# WoordklokCharles.net
KiCad netlist of a schematic drawn in EAGLE
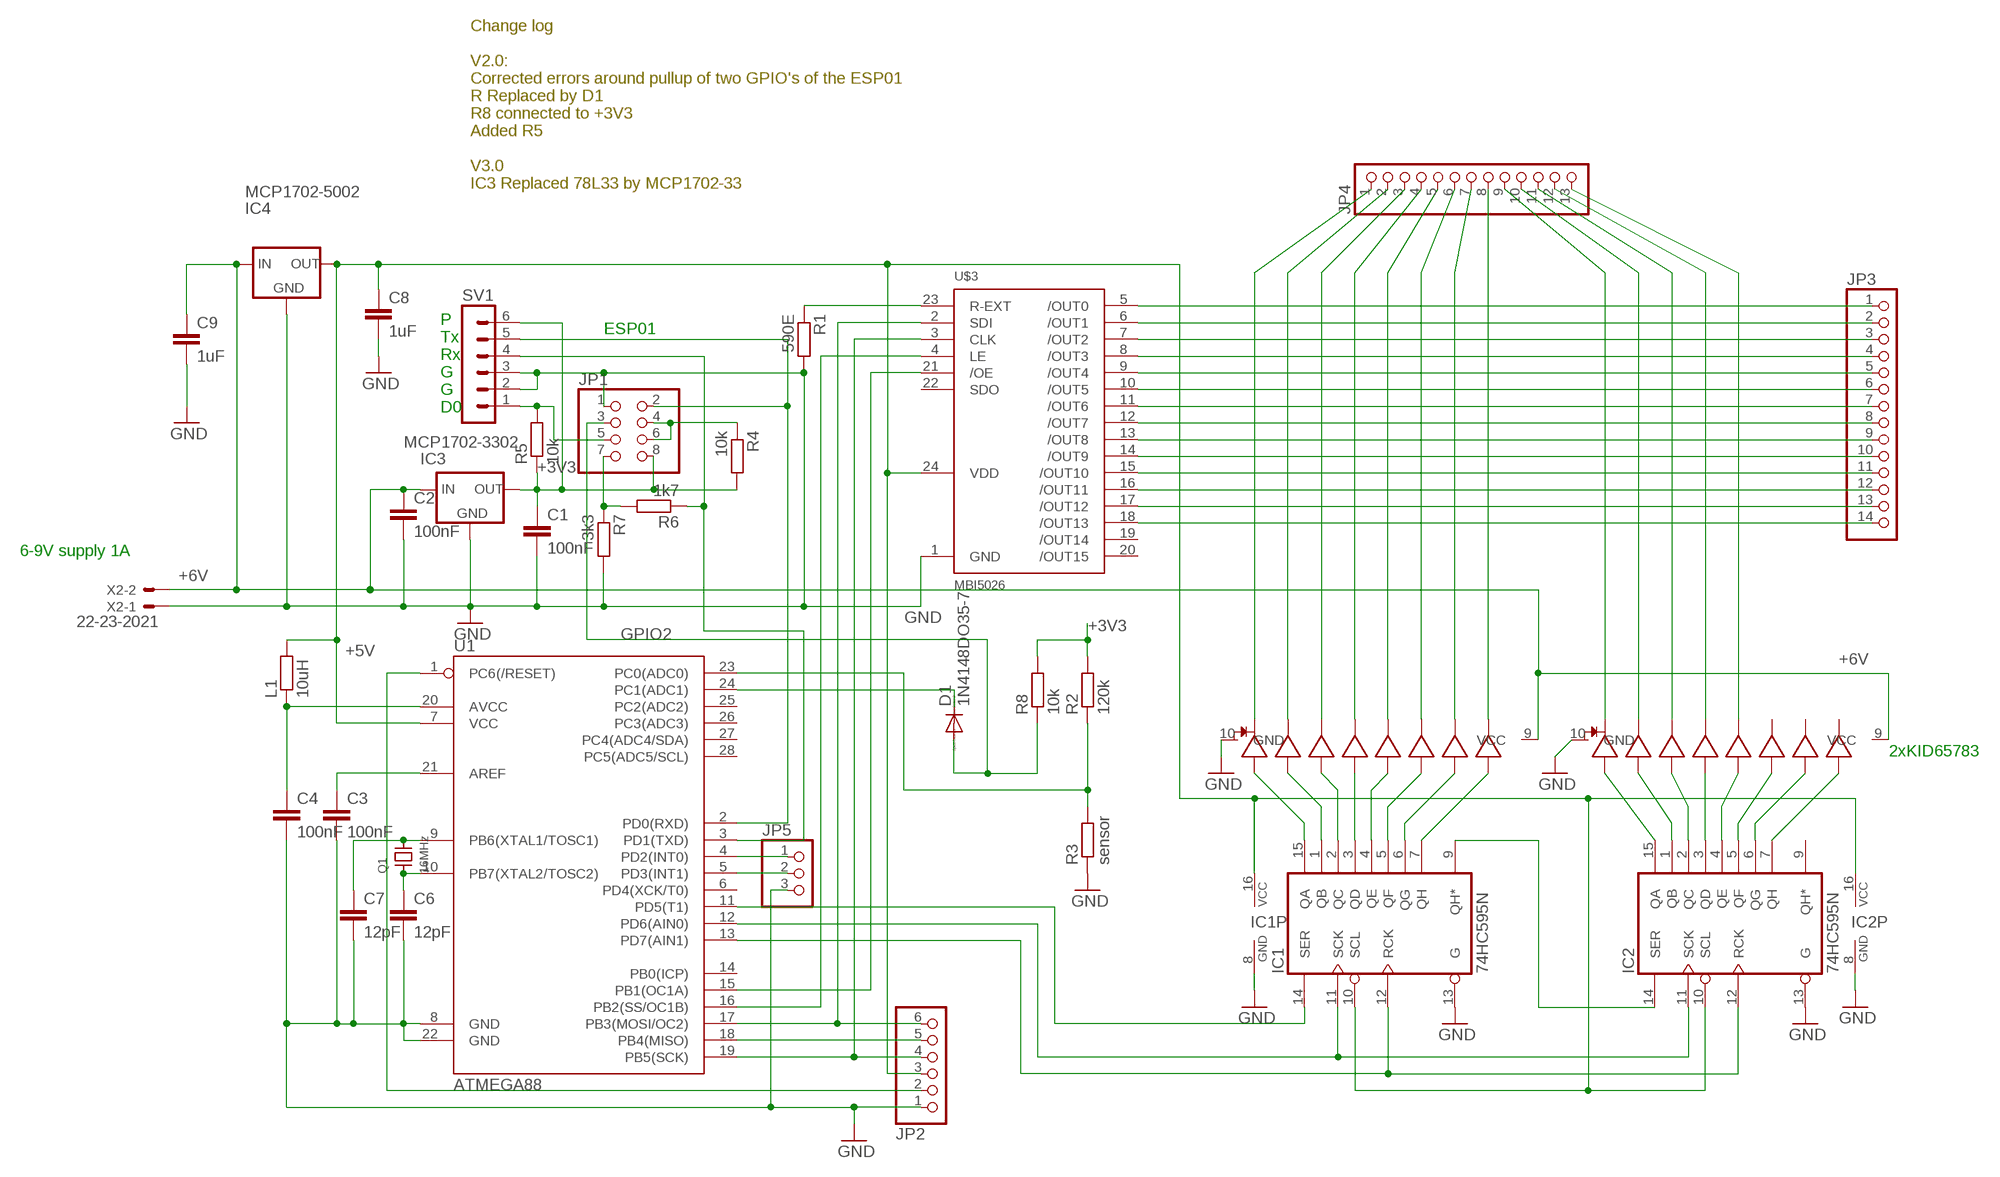
[diagram p0: schematic, sheet 1]

(export (version "E")
  (design (tool "Eeschema 10.0.6"))
  (components
    (comp (ref "C1")
      (value "100nF")
      (footprint "eagle-import:C025-024X044")
      (libsource (lib "eagle-import") (part "C-EU025-024X044"))
    )
    (comp (ref "C2")
      (value "100nF")
      (footprint "eagle-import:C025-024X044")
      (libsource (lib "eagle-import") (part "C-EU025-024X044"))
    )
    (comp (ref "C3")
      (value "100nF")
      (footprint "eagle-import:C025-024X044")
      (libsource (lib "eagle-import") (part "C-EU025-024X044"))
    )
    (comp (ref "C4")
      (value "100nF")
      (footprint "eagle-import:C025-024X044")
      (libsource (lib "eagle-import") (part "C-EU025-024X044"))
    )
    (comp (ref "C6")
      (value "12pF")
      (footprint "eagle-import:C025-024X044")
      (libsource (lib "eagle-import") (part "C-EU025-024X044"))
    )
    (comp (ref "C7")
      (value "12pF")
      (footprint "eagle-import:C025-024X044")
      (libsource (lib "eagle-import") (part "C-EU025-024X044"))
    )
    (comp (ref "C8")
      (value "1uF")
      (footprint "eagle-import:C025-024X044")
      (libsource (lib "eagle-import") (part "C-EU025-024X044"))
    )
    (comp (ref "C9")
      (value "1uF")
      (footprint "eagle-import:C025-024X044")
      (libsource (lib "eagle-import") (part "C-EU025-024X044"))
    )
    (comp (ref "D1")
      (value "1N4148DO35-7")
      (footprint "eagle-import:DO35-7")
      (libsource (lib "eagle-import") (part "1N4148DO35-7"))
    )
    (comp (ref "IC1")
      (value "74HC595N")
      (footprint "eagle-import:DIL16")
      (libsource (lib "eagle-import") (part "74595NHC"))
    )
    (comp (ref "IC2")
      (value "74HC595N")
      (footprint "eagle-import:DIL16")
      (libsource (lib "eagle-import") (part "74595NHC"))
    )
    (comp (ref "IC3")
      (value "MCP1702-3302")
      (footprint "eagle-import:TO92")
      (libsource (lib "eagle-import") (part "MCP1700TRI"))
    )
    (comp (ref "IC4")
      (value "MCP1702-5002")
      (footprint "eagle-import:TO92")
      (libsource (lib "eagle-import") (part "MCP1700TRI"))
    )
    (comp (ref "JP1")
      (value "PINHD-2X4")
      (footprint "eagle-import:2X04")
      (libsource (lib "eagle-import") (part "PINHD-2X4"))
    )
    (comp (ref "JP2")
      (value "PINHD-1X6")
      (footprint "eagle-import:1X06")
      (libsource (lib "eagle-import") (part "PINHD-1X6"))
    )
    (comp (ref "JP3")
      (value "PINHD-1X14")
      (footprint "eagle-import:1X14")
      (libsource (lib "eagle-import") (part "PINHD-1X14"))
    )
    (comp (ref "JP4")
      (value "PINHD-1X13")
      (footprint "eagle-import:1X13")
      (libsource (lib "eagle-import") (part "PINHD-1X13"))
    )
    (comp (ref "JP5")
      (value "PINHD-1X3")
      (footprint "eagle-import:1X03")
      (libsource (lib "eagle-import") (part "PINHD-1X3"))
    )
    (comp (ref "L1")
      (value "10uH")
      (footprint "eagle-import:0204_7")
      (libsource (lib "eagle-import") (part "R-EU_0204/7"))
    )
    (comp (ref "Q1")
      (value "16MHz")
      (footprint "eagle-import:XTAL")
      (libsource (lib "eagle-import") (part "XTAL"))
    )
    (comp (ref "R1")
      (value "590E")
      (footprint "eagle-import:0204_7")
      (libsource (lib "eagle-import") (part "R-EU_0204/7"))
    )
    (comp (ref "R2")
      (value "120k")
      (footprint "eagle-import:0204_7")
      (libsource (lib "eagle-import") (part "R-EU_0204/7"))
    )
    (comp (ref "R3")
      (value "sensor")
      (footprint "eagle-import:0204_7")
      (libsource (lib "eagle-import") (part "R-EU_0204/7"))
    )
    (comp (ref "R4")
      (value "10k")
      (footprint "eagle-import:0204V")
      (libsource (lib "eagle-import") (part "R-EU_0204/2V"))
    )
    (comp (ref "R5")
      (value "10k")
      (footprint "eagle-import:0204V")
      (libsource (lib "eagle-import") (part "R-EU_0204/2V"))
    )
    (comp (ref "R6")
      (value "1k7")
      (footprint "eagle-import:0204_7")
      (libsource (lib "eagle-import") (part "R-EU_0204/7"))
    )
    (comp (ref "R7")
      (value "3k3")
      (footprint "eagle-import:0204_7")
      (libsource (lib "eagle-import") (part "R-EU_0204/7"))
    )
    (comp (ref "R8")
      (value "10k")
      (footprint "eagle-import:0204_7")
      (libsource (lib "eagle-import") (part "R-EU_0204/7"))
    )
    (comp (ref "SV1")
      (value "MA06-1")
      (footprint "eagle-import:MA06-1")
      (libsource (lib "eagle-import") (part "MA06-1"))
    )
    (comp (ref "U$1")
      (value "KID65783")
      (footprint "eagle-import:DIP18")
      (libsource (lib "eagle-import") (part "KID65783DIPDIP18"))
    )
    (comp (ref "U$2")
      (value "KID65783")
      (footprint "eagle-import:DIP18")
      (libsource (lib "eagle-import") (part "KID65783DIPDIP18"))
    )
    (comp (ref "U$3")
      (value "MBI5026")
      (footprint "eagle-import:DIP24")
      (libsource (lib "eagle-import") (part "MBI5026DIP"))
    )
    (comp (ref "U1")
      (value "ATMEGA88")
      (footprint "eagle-import:DIL28-3")
      (libsource (lib "eagle-import") (part "ATMEGA328P_PDIP"))
    )
    (comp (ref "X2")
      (value "22-23-2021")
      (footprint "eagle-import:22-23-2021")
      (fields (field (name "MF") "MOLEX"))
      (libsource (lib "eagle-import") (part "22-23-2021"))
    )
  )
  (nets
    (net (code "1") (name "/+3V3") (class "Default")
      (node (ref "C1") (pin "1") (pinfunction "1_1") (pintype "passive"))
      (node (ref "IC3") (pin "3") (pinfunction "OUT_3") (pintype "passive"))
      (node (ref "JP1") (pin "8") (pinfunction "8_8") (pintype "passive"))
      (node (ref "R2") (pin "2") (pinfunction "2_2") (pintype "passive"))
      (node (ref "R4") (pin "2") (pinfunction "2_2") (pintype "passive"))
      (node (ref "R5") (pin "1") (pinfunction "1_1") (pintype "passive"))
      (node (ref "R8") (pin "2") (pinfunction "2_2") (pintype "passive"))
      (node (ref "SV1") (pin "6") (pinfunction "6_6") (pintype "passive"))
    )
    (net (code "2") (name "/+5V") (class "Default")
      (node (ref "C8") (pin "1") (pinfunction "1_1") (pintype "passive"))
      (node (ref "IC1") (pin "10") (pinfunction "SCL_10") (pintype "input"))
      (node (ref "IC1") (pin "16") (pinfunction "VCC_16") (pintype "power_in"))
      (node (ref "IC2") (pin "10") (pinfunction "SCL_10") (pintype "input"))
      (node (ref "IC2") (pin "16") (pinfunction "VCC_16") (pintype "power_in"))
      (node (ref "IC4") (pin "3") (pinfunction "OUT_3") (pintype "passive"))
      (node (ref "JP2") (pin "3") (pinfunction "3_3") (pintype "passive"))
      (node (ref "L1") (pin "2") (pinfunction "2_2") (pintype "passive"))
      (node (ref "U$3") (pin "24") (pinfunction "VDD_24") (pintype "bidirectional"))
      (node (ref "U1") (pin "7") (pinfunction "VCC_7") (pintype "bidirectional"))
    )
    (net (code "3") (name "/+6V") (class "Default")
      (node (ref "C2") (pin "1") (pinfunction "1_1") (pintype "passive"))
      (node (ref "C9") (pin "1") (pinfunction "1_1") (pintype "passive"))
      (node (ref "IC3") (pin "2") (pinfunction "IN_2") (pintype "input"))
      (node (ref "IC4") (pin "2") (pinfunction "IN_2") (pintype "input"))
      (node (ref "U$1") (pin "9") (pinfunction "VCC_9") (pintype "power_in"))
      (node (ref "U$2") (pin "9") (pinfunction "VCC_9") (pintype "power_in"))
      (node (ref "X2") (pin "2") (pinfunction "S_2") (pintype "passive"))
    )
    (net (code "4") (name "/GPIO2") (class "Default")
      (node (ref "D1") (pin "A") (pinfunction "A_A") (pintype "passive"))
      (node (ref "JP1") (pin "3") (pinfunction "3_3") (pintype "passive"))
      (node (ref "R8") (pin "1") (pinfunction "1_1") (pintype "passive"))
    )
    (net (code "5") (name "GND") (class "Default")
      (node (ref "C1") (pin "2") (pinfunction "2_2") (pintype "passive"))
      (node (ref "C2") (pin "2") (pinfunction "2_2") (pintype "passive"))
      (node (ref "C3") (pin "2") (pinfunction "2_2") (pintype "passive"))
      (node (ref "C4") (pin "2") (pinfunction "2_2") (pintype "passive"))
      (node (ref "C6") (pin "2") (pinfunction "2_2") (pintype "passive"))
      (node (ref "C7") (pin "2") (pinfunction "2_2") (pintype "passive"))
      (node (ref "C8") (pin "2") (pinfunction "2_2") (pintype "passive"))
      (node (ref "C9") (pin "2") (pinfunction "2_2") (pintype "passive"))
      (node (ref "IC1") (pin "13") (pinfunction "G_13") (pintype "input"))
      (node (ref "IC1") (pin "8") (pinfunction "GND_8") (pintype "power_in"))
      (node (ref "IC2") (pin "13") (pinfunction "G_13") (pintype "input"))
      (node (ref "IC2") (pin "8") (pinfunction "GND_8") (pintype "power_in"))
      (node (ref "IC3") (pin "1") (pinfunction "GND_1") (pintype "input"))
      (node (ref "IC4") (pin "1") (pinfunction "GND_1") (pintype "input"))
      (node (ref "JP1") (pin "1") (pinfunction "1_1") (pintype "passive"))
      (node (ref "JP2") (pin "1") (pinfunction "1_1") (pintype "passive"))
      (node (ref "JP5") (pin "3") (pinfunction "3_3") (pintype "passive"))
      (node (ref "R1") (pin "2") (pinfunction "2_2") (pintype "passive"))
      (node (ref "R3") (pin "1") (pinfunction "1_1") (pintype "passive"))
      (node (ref "R7") (pin "2") (pinfunction "2_2") (pintype "passive"))
      (node (ref "SV1") (pin "2") (pinfunction "2_2") (pintype "passive"))
      (node (ref "SV1") (pin "3") (pinfunction "3_3") (pintype "passive"))
      (node (ref "U$1") (pin "10") (pinfunction "GND_10") (pintype "power_in"))
      (node (ref "U$2") (pin "10") (pinfunction "GND_10") (pintype "power_in"))
      (node (ref "U$3") (pin "1") (pinfunction "GND_1") (pintype "bidirectional"))
      (node (ref "U1") (pin "22") (pinfunction "GND_22") (pintype "bidirectional"))
      (node (ref "U1") (pin "8") (pinfunction "GND_8") (pintype "bidirectional"))
      (node (ref "X2") (pin "1") (pinfunction "S_1") (pintype "passive"))
    )
    (net (code "6") (name "Net-(IC1A-QA)") (class "Default")
      (node (ref "IC1") (pin "15") (pinfunction "QA_15") (pintype "tri_state"))
      (node (ref "U$1") (pin "8") (pinfunction "IN7_8") (pintype "input"))
    )
    (net (code "7") (name "Net-(IC1A-QB)") (class "Default")
      (node (ref "IC1") (pin "1") (pinfunction "QB_1") (pintype "tri_state"))
      (node (ref "U$1") (pin "7") (pinfunction "IN6_7") (pintype "input"))
    )
    (net (code "8") (name "Net-(IC1A-QC)") (class "Default")
      (node (ref "IC1") (pin "2") (pinfunction "QC_2") (pintype "tri_state"))
      (node (ref "U$1") (pin "6") (pinfunction "IN5_6") (pintype "input"))
    )
    (net (code "9") (name "Net-(IC1A-QD)") (class "Default")
      (node (ref "IC1") (pin "3") (pinfunction "QD_3") (pintype "tri_state"))
      (node (ref "U$1") (pin "5") (pinfunction "IN4_5") (pintype "input"))
    )
    (net (code "10") (name "Net-(IC1A-QE)") (class "Default")
      (node (ref "IC1") (pin "4") (pinfunction "QE_4") (pintype "tri_state"))
      (node (ref "U$1") (pin "4") (pinfunction "IN3_4") (pintype "input"))
    )
    (net (code "11") (name "Net-(IC1A-QF)") (class "Default")
      (node (ref "IC1") (pin "5") (pinfunction "QF_5") (pintype "tri_state"))
      (node (ref "U$1") (pin "3") (pinfunction "IN2_3") (pintype "input"))
    )
    (net (code "12") (name "Net-(IC1A-QG)") (class "Default")
      (node (ref "IC1") (pin "6") (pinfunction "QG_6") (pintype "tri_state"))
      (node (ref "U$1") (pin "2") (pinfunction "IN1_2") (pintype "input"))
    )
    (net (code "13") (name "Net-(IC1A-QH)") (class "Default")
      (node (ref "IC1") (pin "7") (pinfunction "QH_7") (pintype "tri_state"))
      (node (ref "U$1") (pin "1") (pinfunction "IN0_1") (pintype "input"))
    )
    (net (code "14") (name "Net-(IC1A-QH*)") (class "Default")
      (node (ref "IC1") (pin "9") (pinfunction "QH*_9") (pintype "tri_state"))
      (node (ref "IC2") (pin "14") (pinfunction "SER_14") (pintype "input"))
    )
    (net (code "15") (name "Net-(IC1A-RCK)") (class "Default")
      (node (ref "IC1") (pin "12") (pinfunction "RCK_12") (pintype "input"))
      (node (ref "IC2") (pin "12") (pinfunction "RCK_12") (pintype "input"))
      (node (ref "U1") (pin "13") (pinfunction "PD7(AIN1)_13") (pintype "bidirectional"))
    )
    (net (code "16") (name "Net-(IC1A-SCK)") (class "Default")
      (node (ref "IC1") (pin "11") (pinfunction "SCK_11") (pintype "input"))
      (node (ref "IC2") (pin "11") (pinfunction "SCK_11") (pintype "input"))
      (node (ref "U1") (pin "12") (pinfunction "PD6(AIN0)_12") (pintype "bidirectional"))
    )
    (net (code "17") (name "Net-(IC1A-SER)") (class "Default")
      (node (ref "IC1") (pin "14") (pinfunction "SER_14") (pintype "input"))
      (node (ref "U1") (pin "11") (pinfunction "PD5(T1)_11") (pintype "bidirectional"))
    )
    (net (code "18") (name "Net-(IC2A-QA)") (class "Default")
      (node (ref "IC2") (pin "15") (pinfunction "QA_15") (pintype "tri_state"))
      (node (ref "U$2") (pin "8") (pinfunction "IN7_8") (pintype "input"))
    )
    (net (code "19") (name "Net-(IC2A-QB)") (class "Default")
      (node (ref "IC2") (pin "1") (pinfunction "QB_1") (pintype "tri_state"))
      (node (ref "U$2") (pin "7") (pinfunction "IN6_7") (pintype "input"))
    )
    (net (code "20") (name "Net-(IC2A-QC)") (class "Default")
      (node (ref "IC2") (pin "2") (pinfunction "QC_2") (pintype "tri_state"))
      (node (ref "U$2") (pin "6") (pinfunction "IN5_6") (pintype "input"))
    )
    (net (code "21") (name "Net-(IC2A-QD)") (class "Default")
      (node (ref "IC2") (pin "3") (pinfunction "QD_3") (pintype "tri_state"))
      (node (ref "U$2") (pin "5") (pinfunction "IN4_5") (pintype "input"))
    )
    (net (code "22") (name "Net-(IC2A-QE)") (class "Default")
      (node (ref "IC2") (pin "4") (pinfunction "QE_4") (pintype "tri_state"))
      (node (ref "U$2") (pin "4") (pinfunction "IN3_4") (pintype "input"))
    )
    (net (code "23") (name "Net-(IC2A-QF)") (class "Default")
      (node (ref "IC2") (pin "5") (pinfunction "QF_5") (pintype "tri_state"))
      (node (ref "U$2") (pin "3") (pinfunction "IN2_3") (pintype "input"))
    )
    (net (code "24") (name "Net-(IC2A-QG)") (class "Default")
      (node (ref "IC2") (pin "6") (pinfunction "QG_6") (pintype "tri_state"))
      (node (ref "U$2") (pin "2") (pinfunction "IN1_2") (pintype "input"))
    )
    (net (code "25") (name "Net-(IC2A-QH)") (class "Default")
      (node (ref "IC2") (pin "7") (pinfunction "QH_7") (pintype "tri_state"))
      (node (ref "U$2") (pin "1") (pinfunction "IN0_1") (pintype "input"))
    )
    (net (code "26") (name "Net-(JP1-Pad4)") (class "Default")
      (node (ref "JP1") (pin "4") (pinfunction "4_4") (pintype "passive"))
      (node (ref "JP1") (pin "6") (pinfunction "6_6") (pintype "passive"))
      (node (ref "R4") (pin "1") (pinfunction "1_1") (pintype "passive"))
    )
    (net (code "27") (name "Net-(JP1-Pad5)") (class "Default")
      (node (ref "JP1") (pin "5") (pinfunction "5_5") (pintype "passive"))
      (node (ref "R5") (pin "2") (pinfunction "2_2") (pintype "passive"))
      (node (ref "SV1") (pin "1") (pinfunction "1_1") (pintype "passive"))
    )
    (net (code "28") (name "Net-(JP1-Pad7)") (class "Default")
      (node (ref "JP1") (pin "7") (pinfunction "7_7") (pintype "passive"))
      (node (ref "R6") (pin "2") (pinfunction "2_2") (pintype "passive"))
      (node (ref "R7") (pin "1") (pinfunction "1_1") (pintype "passive"))
    )
    (net (code "29") (name "Net-(U$1-OUT0)") (class "Default")
      (node (ref "JP4") (pin "8") (pinfunction "8_8") (pintype "passive"))
      (node (ref "U$1") (pin "18") (pinfunction "OUT0_18") (pintype "output"))
    )
    (net (code "30") (name "Net-(U$1-OUT1)") (class "Default")
      (node (ref "JP4") (pin "7") (pinfunction "7_7") (pintype "passive"))
      (node (ref "U$1") (pin "17") (pinfunction "OUT1_17") (pintype "output"))
    )
    (net (code "31") (name "Net-(U$1-OUT2)") (class "Default")
      (node (ref "JP4") (pin "6") (pinfunction "6_6") (pintype "passive"))
      (node (ref "U$1") (pin "16") (pinfunction "OUT2_16") (pintype "output"))
    )
    (net (code "32") (name "Net-(U$1-OUT3)") (class "Default")
      (node (ref "JP4") (pin "5") (pinfunction "5_5") (pintype "passive"))
      (node (ref "U$1") (pin "15") (pinfunction "OUT3_15") (pintype "output"))
    )
    (net (code "33") (name "Net-(U$1-OUT4)") (class "Default")
      (node (ref "JP4") (pin "4") (pinfunction "4_4") (pintype "passive"))
      (node (ref "U$1") (pin "14") (pinfunction "OUT4_14") (pintype "output"))
    )
    (net (code "34") (name "Net-(U$1-OUT5)") (class "Default")
      (node (ref "JP4") (pin "3") (pinfunction "3_3") (pintype "passive"))
      (node (ref "U$1") (pin "13") (pinfunction "OUT5_13") (pintype "output"))
    )
    (net (code "35") (name "Net-(U$1-OUT6)") (class "Default")
      (node (ref "JP4") (pin "2") (pinfunction "2_2") (pintype "passive"))
      (node (ref "U$1") (pin "12") (pinfunction "OUT6_12") (pintype "output"))
    )
    (net (code "36") (name "Net-(U$1-OUT7)") (class "Default")
      (node (ref "JP4") (pin "1") (pinfunction "1_1") (pintype "passive"))
      (node (ref "U$1") (pin "11") (pinfunction "OUT7_11") (pintype "output"))
    )
    (net (code "37") (name "Net-(U$2-OUT3)") (class "Default")
      (node (ref "JP4") (pin "13") (pinfunction "13_13") (pintype "passive"))
      (node (ref "U$2") (pin "15") (pinfunction "OUT3_15") (pintype "output"))
    )
    (net (code "38") (name "Net-(U$2-OUT4)") (class "Default")
      (node (ref "JP4") (pin "12") (pinfunction "12_12") (pintype "passive"))
      (node (ref "U$2") (pin "14") (pinfunction "OUT4_14") (pintype "output"))
    )
    (net (code "39") (name "Net-(U$2-OUT5)") (class "Default")
      (node (ref "JP4") (pin "11") (pinfunction "11_11") (pintype "passive"))
      (node (ref "U$2") (pin "13") (pinfunction "OUT5_13") (pintype "output"))
    )
    (net (code "40") (name "Net-(U$2-OUT6)") (class "Default")
      (node (ref "JP4") (pin "10") (pinfunction "10_10") (pintype "passive"))
      (node (ref "U$2") (pin "12") (pinfunction "OUT6_12") (pintype "output"))
    )
    (net (code "41") (name "Net-(U$2-OUT7)") (class "Default")
      (node (ref "JP4") (pin "9") (pinfunction "9_9") (pintype "passive"))
      (node (ref "U$2") (pin "11") (pinfunction "OUT7_11") (pintype "output"))
    )
    (net (code "42") (name "Net-(U$3-CLK)") (class "Default")
      (node (ref "JP2") (pin "4") (pinfunction "4_4") (pintype "passive"))
      (node (ref "U$3") (pin "3") (pinfunction "CLK_3") (pintype "bidirectional"))
      (node (ref "U1") (pin "19") (pinfunction "PB5(SCK)_19") (pintype "bidirectional"))
    )
    (net (code "43") (name "Net-(U$3-LE)") (class "Default")
      (node (ref "U$3") (pin "4") (pinfunction "LE_4") (pintype "bidirectional"))
      (node (ref "U1") (pin "16") (pinfunction "PB2(SS/OC1B)_16") (pintype "bidirectional"))
    )
    (net (code "44") (name "Net-(U$3-R-EXT)") (class "Default")
      (node (ref "R1") (pin "1") (pinfunction "1_1") (pintype "passive"))
      (node (ref "U$3") (pin "23") (pinfunction "R-EXT_23") (pintype "bidirectional"))
    )
    (net (code "45") (name "Net-(U$3-SDI)") (class "Default")
      (node (ref "JP2") (pin "6") (pinfunction "6_6") (pintype "passive"))
      (node (ref "U$3") (pin "2") (pinfunction "SDI_2") (pintype "bidirectional"))
      (node (ref "U1") (pin "17") (pinfunction "PB3(MOSI/OC2)_17") (pintype "bidirectional"))
    )
    (net (code "46") (name "Net-(U$3-{slash}OE)") (class "Default")
      (node (ref "U$3") (pin "21") (pinfunction "/OE_21") (pintype "bidirectional"))
      (node (ref "U1") (pin "15") (pinfunction "PB1(OC1A)_15") (pintype "bidirectional"))
    )
    (net (code "47") (name "Net-(U$3-{slash}OUT0)") (class "Default")
      (node (ref "JP3") (pin "1") (pinfunction "1_1") (pintype "passive"))
      (node (ref "U$3") (pin "5") (pinfunction "/OUT0_5") (pintype "bidirectional"))
    )
    (net (code "48") (name "Net-(U$3-{slash}OUT1)") (class "Default")
      (node (ref "JP3") (pin "2") (pinfunction "2_2") (pintype "passive"))
      (node (ref "U$3") (pin "6") (pinfunction "/OUT1_6") (pintype "bidirectional"))
    )
    (net (code "49") (name "Net-(U$3-{slash}OUT2)") (class "Default")
      (node (ref "JP3") (pin "3") (pinfunction "3_3") (pintype "passive"))
      (node (ref "U$3") (pin "7") (pinfunction "/OUT2_7") (pintype "bidirectional"))
    )
    (net (code "50") (name "Net-(U$3-{slash}OUT3)") (class "Default")
      (node (ref "JP3") (pin "4") (pinfunction "4_4") (pintype "passive"))
      (node (ref "U$3") (pin "8") (pinfunction "/OUT3_8") (pintype "bidirectional"))
    )
    (net (code "51") (name "Net-(U$3-{slash}OUT4)") (class "Default")
      (node (ref "JP3") (pin "5") (pinfunction "5_5") (pintype "passive"))
      (node (ref "U$3") (pin "9") (pinfunction "/OUT4_9") (pintype "bidirectional"))
    )
    (net (code "52") (name "Net-(U$3-{slash}OUT5)") (class "Default")
      (node (ref "JP3") (pin "6") (pinfunction "6_6") (pintype "passive"))
      (node (ref "U$3") (pin "10") (pinfunction "/OUT5_10") (pintype "bidirectional"))
    )
    (net (code "53") (name "Net-(U$3-{slash}OUT6)") (class "Default")
      (node (ref "JP3") (pin "7") (pinfunction "7_7") (pintype "passive"))
      (node (ref "U$3") (pin "11") (pinfunction "/OUT6_11") (pintype "bidirectional"))
    )
    (net (code "54") (name "Net-(U$3-{slash}OUT7)") (class "Default")
      (node (ref "JP3") (pin "8") (pinfunction "8_8") (pintype "passive"))
      (node (ref "U$3") (pin "12") (pinfunction "/OUT7_12") (pintype "bidirectional"))
    )
    (net (code "55") (name "Net-(U$3-{slash}OUT8)") (class "Default")
      (node (ref "JP3") (pin "9") (pinfunction "9_9") (pintype "passive"))
      (node (ref "U$3") (pin "13") (pinfunction "/OUT8_13") (pintype "bidirectional"))
    )
    (net (code "56") (name "Net-(U$3-{slash}OUT9)") (class "Default")
      (node (ref "JP3") (pin "10") (pinfunction "10_10") (pintype "passive"))
      (node (ref "U$3") (pin "14") (pinfunction "/OUT9_14") (pintype "bidirectional"))
    )
    (net (code "57") (name "Net-(U$3-{slash}OUT10)") (class "Default")
      (node (ref "JP3") (pin "11") (pinfunction "11_11") (pintype "passive"))
      (node (ref "U$3") (pin "15") (pinfunction "/OUT10_15") (pintype "bidirectional"))
    )
    (net (code "58") (name "Net-(U$3-{slash}OUT11)") (class "Default")
      (node (ref "JP3") (pin "12") (pinfunction "12_12") (pintype "passive"))
      (node (ref "U$3") (pin "16") (pinfunction "/OUT11_16") (pintype "bidirectional"))
    )
    (net (code "59") (name "Net-(U$3-{slash}OUT12)") (class "Default")
      (node (ref "JP3") (pin "13") (pinfunction "13_13") (pintype "passive"))
      (node (ref "U$3") (pin "17") (pinfunction "/OUT12_17") (pintype "bidirectional"))
    )
    (net (code "60") (name "Net-(U$3-{slash}OUT13)") (class "Default")
      (node (ref "JP3") (pin "14") (pinfunction "14_14") (pintype "passive"))
      (node (ref "U$3") (pin "18") (pinfunction "/OUT13_18") (pintype "bidirectional"))
    )
    (net (code "61") (name "Net-(U1-AREF)") (class "Default")
      (node (ref "C3") (pin "1") (pinfunction "1_1") (pintype "passive"))
      (node (ref "U1") (pin "21") (pinfunction "AREF_21") (pintype "bidirectional"))
    )
    (net (code "62") (name "Net-(U1-AVCC)") (class "Default")
      (node (ref "C4") (pin "1") (pinfunction "1_1") (pintype "passive"))
      (node (ref "L1") (pin "1") (pinfunction "1_1") (pintype "passive"))
      (node (ref "U1") (pin "20") (pinfunction "AVCC_20") (pintype "bidirectional"))
    )
    (net (code "63") (name "Net-(U1-PB4(MISO))") (class "Default")
      (node (ref "JP2") (pin "5") (pinfunction "5_5") (pintype "passive"))
      (node (ref "U1") (pin "18") (pinfunction "PB4(MISO)_18") (pintype "bidirectional"))
    )
    (net (code "64") (name "Net-(U1-PB6(XTAL1{slash}TOSC1))") (class "Default")
      (node (ref "C7") (pin "1") (pinfunction "1_1") (pintype "passive"))
      (node (ref "Q1") (pin "P$2") (pinfunction "P$2_P$2") (pintype "bidirectional"))
      (node (ref "U1") (pin "9") (pinfunction "PB6(XTAL1/TOSC1)_9") (pintype "bidirectional"))
    )
    (net (code "65") (name "Net-(U1-PB7(XTAL2{slash}TOSC2))") (class "Default")
      (node (ref "C6") (pin "1") (pinfunction "1_1") (pintype "passive"))
      (node (ref "Q1") (pin "P$1") (pinfunction "P$1_P$1") (pintype "bidirectional"))
      (node (ref "U1") (pin "10") (pinfunction "PB7(XTAL2/TOSC2)_10") (pintype "bidirectional"))
    )
    (net (code "66") (name "Net-(U1-PC0(ADC0))") (class "Default")
      (node (ref "R2") (pin "1") (pinfunction "1_1") (pintype "passive"))
      (node (ref "R3") (pin "2") (pinfunction "2_2") (pintype "passive"))
      (node (ref "U1") (pin "23") (pinfunction "PC0(ADC0)_23") (pintype "bidirectional"))
    )
    (net (code "67") (name "Net-(U1-PC1(ADC1))") (class "Default")
      (node (ref "D1") (pin "C") (pinfunction "C_C") (pintype "passive"))
      (node (ref "U1") (pin "24") (pinfunction "PC1(ADC1)_24") (pintype "bidirectional"))
    )
    (net (code "68") (name "Net-(U1-PC6({slash}RESET))") (class "Default")
      (node (ref "JP2") (pin "2") (pinfunction "2_2") (pintype "passive"))
      (node (ref "U1") (pin "1") (pinfunction "PC6(/RESET)_1") (pintype "bidirectional"))
    )
    (net (code "69") (name "Net-(U1-PD0(RXD))") (class "Default")
      (node (ref "JP1") (pin "2") (pinfunction "2_2") (pintype "passive"))
      (node (ref "SV1") (pin "5") (pinfunction "5_5") (pintype "passive"))
      (node (ref "U1") (pin "2") (pinfunction "PD0(RXD)_2") (pintype "bidirectional"))
    )
    (net (code "70") (name "Net-(U1-PD1(TXD))") (class "Default")
      (node (ref "R6") (pin "1") (pinfunction "1_1") (pintype "passive"))
      (node (ref "SV1") (pin "4") (pinfunction "4_4") (pintype "passive"))
      (node (ref "U1") (pin "3") (pinfunction "PD1(TXD)_3") (pintype "bidirectional"))
    )
    (net (code "71") (name "Net-(U1-PD2(INT0))") (class "Default")
      (node (ref "JP5") (pin "1") (pinfunction "1_1") (pintype "passive"))
      (node (ref "U1") (pin "4") (pinfunction "PD2(INT0)_4") (pintype "bidirectional"))
    )
    (net (code "72") (name "Net-(U1-PD3(INT1))") (class "Default")
      (node (ref "JP5") (pin "2") (pinfunction "2_2") (pintype "passive"))
      (node (ref "U1") (pin "5") (pinfunction "PD3(INT1)_5") (pintype "bidirectional"))
    )
    (net (code "73") (name "unconnected-(IC2A-QH*-Pad9)") (class "Default")
      (node (ref "IC2") (pin "9") (pinfunction "QH*_9") (pintype "tri_state"))
    )
    (net (code "74") (name "unconnected-(U$2-OUT0-Pad18)") (class "Default")
      (node (ref "U$2") (pin "18") (pinfunction "OUT0_18") (pintype "output"))
    )
    (net (code "75") (name "unconnected-(U$2-OUT1-Pad17)") (class "Default")
      (node (ref "U$2") (pin "17") (pinfunction "OUT1_17") (pintype "output"))
    )
    (net (code "76") (name "unconnected-(U$2-OUT2-Pad16)") (class "Default")
      (node (ref "U$2") (pin "16") (pinfunction "OUT2_16") (pintype "output"))
    )
    (net (code "77") (name "unconnected-(U$3-SDO-Pad22)") (class "Default")
      (node (ref "U$3") (pin "22") (pinfunction "SDO_22") (pintype "bidirectional"))
    )
    (net (code "78") (name "unconnected-(U$3-{slash}OUT14-Pad19)") (class "Default")
      (node (ref "U$3") (pin "19") (pinfunction "/OUT14_19") (pintype "bidirectional"))
    )
    (net (code "79") (name "unconnected-(U$3-{slash}OUT15-Pad20)") (class "Default")
      (node (ref "U$3") (pin "20") (pinfunction "/OUT15_20") (pintype "bidirectional"))
    )
    (net (code "80") (name "unconnected-(U1-PB0(ICP)-Pad14)") (class "Default")
      (node (ref "U1") (pin "14") (pinfunction "PB0(ICP)_14") (pintype "bidirectional"))
    )
    (net (code "81") (name "unconnected-(U1-PC2(ADC2)-Pad25)") (class "Default")
      (node (ref "U1") (pin "25") (pinfunction "PC2(ADC2)_25") (pintype "bidirectional"))
    )
    (net (code "82") (name "unconnected-(U1-PC3(ADC3)-Pad26)") (class "Default")
      (node (ref "U1") (pin "26") (pinfunction "PC3(ADC3)_26") (pintype "bidirectional"))
    )
    (net (code "83") (name "unconnected-(U1-PC4(ADC4{slash}SDA)-Pad27)") (class "Default")
      (node (ref "U1") (pin "27") (pinfunction "PC4(ADC4/SDA)_27") (pintype "bidirectional"))
    )
    (net (code "84") (name "unconnected-(U1-PC5(ADC5{slash}SCL)-Pad28)") (class "Default")
      (node (ref "U1") (pin "28") (pinfunction "PC5(ADC5/SCL)_28") (pintype "bidirectional"))
    )
    (net (code "85") (name "unconnected-(U1-PD4(XCK{slash}T0)-Pad6)") (class "Default")
      (node (ref "U1") (pin "6") (pinfunction "PD4(XCK/T0)_6") (pintype "bidirectional"))
    )
  )
)
